# t85db.net
KiCad netlist of a schematic drawn in EAGLE
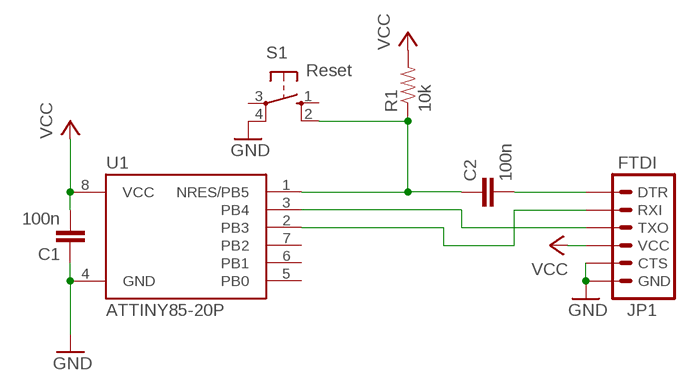
[diagram p0: schematic, sheet 1]

(export (version "E")
  (design (tool "Eeschema 10.0.6"))
  (components
    (comp (ref "C1")
      (value "100n")
      (footprint "eagle-import:CAP-PTH-5MM")
      (libsource (lib "eagle-import") (part "CAPPTH1"))
    )
    (comp (ref "C2")
      (value "100n")
      (footprint "eagle-import:CAP-PTH-5MM")
      (libsource (lib "eagle-import") (part "CAPPTH1"))
    )
    (comp (ref "JP1")
      (value "FTDI")
      (footprint "eagle-import:1X06")
      (libsource (lib "eagle-import") (part "ARDUINO_SERIAL_PROGRAMPTH"))
    )
    (comp (ref "R1")
      (value "10k")
      (footprint "eagle-import:AXIAL-0.1EZ")
      (libsource (lib "eagle-import") (part "RESISTORPTH-1/4W-VERT"))
    )
    (comp (ref "S1")
      (value "Reset")
      (footprint "eagle-import:B3F-10XX")
      (fields (field (name "MPN") "B3F-1000"))
      (libsource (lib "eagle-import") (part "10-XX"))
    )
    (comp (ref "U1")
      (value "ATTINY85-20P")
      (footprint "eagle-import:PDIP08_300MIL")
      (libsource (lib "eagle-import") (part "ATTINY85P-20"))
    )
  )
  (nets
    (net (code "1") (name "GND") (class "Default")
      (node (ref "C1") (pin "1") (pinfunction "1_1") (pintype "passive"))
      (node (ref "JP1") (pin "5") (pinfunction "CTS_5") (pintype "passive"))
      (node (ref "JP1") (pin "6") (pinfunction "GND_6") (pintype "passive"))
      (node (ref "S1") (pin "4") (pinfunction "P1_4") (pintype "passive"))
      (node (ref "U1") (pin "4") (pinfunction "GND_4") (pintype "power_in"))
    )
    (net (code "2") (name "Net-(JP1-DTR)") (class "Default")
      (node (ref "C2") (pin "2") (pinfunction "2_2") (pintype "passive"))
      (node (ref "JP1") (pin "1") (pinfunction "DTR_1") (pintype "passive"))
    )
    (net (code "3") (name "Net-(JP1-RXI)") (class "Default")
      (node (ref "JP1") (pin "2") (pinfunction "RXI_2") (pintype "passive"))
      (node (ref "U1") (pin "2") (pinfunction "PB3_2") (pintype "bidirectional"))
    )
    (net (code "4") (name "Net-(JP1-TXO)") (class "Default")
      (node (ref "JP1") (pin "3") (pinfunction "TXO_3") (pintype "passive"))
      (node (ref "U1") (pin "3") (pinfunction "PB4_3") (pintype "bidirectional"))
    )
    (net (code "5") (name "Net-(R1-1)") (class "Default")
      (node (ref "C2") (pin "1") (pinfunction "1_1") (pintype "passive"))
      (node (ref "R1") (pin "P$1") (pinfunction "1_P$1") (pintype "passive"))
      (node (ref "S1") (pin "2") (pinfunction "S1_2") (pintype "passive"))
      (node (ref "U1") (pin "1") (pinfunction "NRES/PB5_1") (pintype "bidirectional"))
    )
    (net (code "6") (name "VCC") (class "Default")
      (node (ref "C1") (pin "2") (pinfunction "2_2") (pintype "passive"))
      (node (ref "JP1") (pin "4") (pinfunction "VCC_4") (pintype "passive"))
      (node (ref "R1") (pin "P$2") (pinfunction "2_P$2") (pintype "passive"))
      (node (ref "U1") (pin "8") (pinfunction "VCC_8") (pintype "power_in"))
    )
    (net (code "7") (name "unconnected-(S1-P-Pad3)") (class "Default")
      (node (ref "S1") (pin "3") (pinfunction "P_3") (pintype "passive"))
    )
    (net (code "8") (name "unconnected-(S1-S-Pad1)") (class "Default")
      (node (ref "S1") (pin "1") (pinfunction "S_1") (pintype "passive"))
    )
    (net (code "9") (name "unconnected-(U1-PB0-Pad5)") (class "Default")
      (node (ref "U1") (pin "5") (pinfunction "PB0_5") (pintype "bidirectional"))
    )
    (net (code "10") (name "unconnected-(U1-PB1-Pad6)") (class "Default")
      (node (ref "U1") (pin "6") (pinfunction "PB1_6") (pintype "bidirectional"))
    )
    (net (code "11") (name "unconnected-(U1-PB2-Pad7)") (class "Default")
      (node (ref "U1") (pin "7") (pinfunction "PB2_7") (pintype "bidirectional"))
    )
  )
)
